# CPU_Dev_revA_1.net
KiCad netlist of a schematic drawn in EAGLE
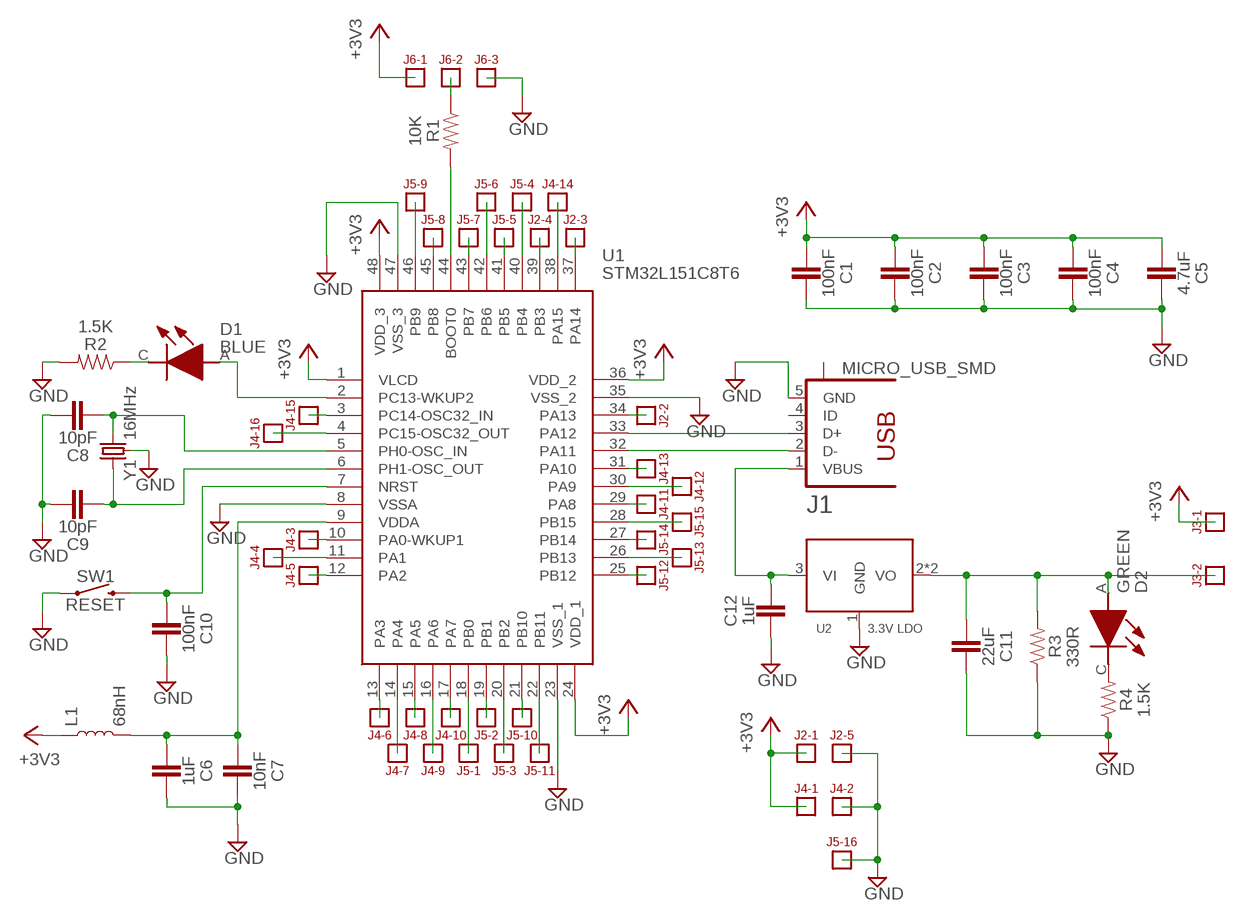
[diagram p0: schematic, sheet 1]

(export (version "E")
  (design (tool "Eeschema 10.0.6"))
  (components
    (comp (ref "C1")
      (value "100nF")
      (footprint "eagle-import:0402")
      (libsource (lib "eagle-import") (part "C_0402"))
    )
    (comp (ref "C2")
      (value "100nF")
      (footprint "eagle-import:0402")
      (libsource (lib "eagle-import") (part "C_0402"))
    )
    (comp (ref "C3")
      (value "100nF")
      (footprint "eagle-import:0402")
      (libsource (lib "eagle-import") (part "C_0402"))
    )
    (comp (ref "C4")
      (value "100nF")
      (footprint "eagle-import:0402")
      (libsource (lib "eagle-import") (part "C_0402"))
    )
    (comp (ref "C5")
      (value "4.7uF")
      (footprint "eagle-import:0402")
      (libsource (lib "eagle-import") (part "C_0402"))
    )
    (comp (ref "C6")
      (value "1uF")
      (footprint "eagle-import:0402")
      (libsource (lib "eagle-import") (part "C_0402"))
    )
    (comp (ref "C7")
      (value "10nF")
      (footprint "eagle-import:0402")
      (libsource (lib "eagle-import") (part "C_0402"))
    )
    (comp (ref "C8")
      (value "10pF")
      (footprint "eagle-import:0402")
      (libsource (lib "eagle-import") (part "C_0402"))
    )
    (comp (ref "C9")
      (value "10pF")
      (footprint "eagle-import:0402")
      (libsource (lib "eagle-import") (part "C_0402"))
    )
    (comp (ref "C10")
      (value "100nF")
      (footprint "eagle-import:0402")
      (libsource (lib "eagle-import") (part "C_0402"))
    )
    (comp (ref "C11")
      (value "22uF")
      (footprint "eagle-import:1206")
      (libsource (lib "eagle-import") (part "C_1206"))
    )
    (comp (ref "C12")
      (value "1uF")
      (footprint "eagle-import:0402")
      (libsource (lib "eagle-import") (part "C_0402"))
    )
    (comp (ref "D1")
      (value "BLUE")
      (footprint "eagle-import:LED_0603")
      (libsource (lib "eagle-import") (part "LED_0603"))
    )
    (comp (ref "D2")
      (value "GREEN")
      (footprint "eagle-import:LED_0603")
      (libsource (lib "eagle-import") (part "LED_0603"))
    )
    (comp (ref "J1")
      (value "MICRO_USB_SMD")
      (footprint "eagle-import:10118192-0002LF")
      (libsource (lib "eagle-import") (part "MICRO_USB_SMD"))
    )
    (comp (ref "J2")
      (value "HEADER_5PIN")
      (footprint "eagle-import:HEADER_5PIN")
      (libsource (lib "eagle-import") (part "HEADER_5PIN"))
    )
    (comp (ref "J3")
      (value "HEADER_2PIN")
      (footprint "eagle-import:HEADER_2PIN")
      (libsource (lib "eagle-import") (part "HEADER_2PIN"))
    )
    (comp (ref "J4")
      (value "HEADER_16PIN")
      (footprint "eagle-import:HEADER_16PIN")
      (libsource (lib "eagle-import") (part "HEADER_16PIN"))
    )
    (comp (ref "J5")
      (value "HEADER_16PIN")
      (footprint "eagle-import:HEADER_16PIN")
      (libsource (lib "eagle-import") (part "HEADER_16PIN"))
    )
    (comp (ref "J6")
      (value "HEADER_3PIN")
      (footprint "eagle-import:HEADER_3PIN")
      (libsource (lib "eagle-import") (part "HEADER_3PIN"))
    )
    (comp (ref "L1")
      (value "68nH")
      (footprint "eagle-import:0603")
      (libsource (lib "eagle-import") (part "L_0603"))
    )
    (comp (ref "R1")
      (value "10K")
      (footprint "eagle-import:0402")
      (libsource (lib "eagle-import") (part "R_0402"))
    )
    (comp (ref "R2")
      (value "1.5K")
      (footprint "eagle-import:0402")
      (libsource (lib "eagle-import") (part "R_0402"))
    )
    (comp (ref "R3")
      (value "330R")
      (footprint "eagle-import:0402")
      (libsource (lib "eagle-import") (part "R_0402"))
    )
    (comp (ref "R4")
      (value "1.5K")
      (footprint "eagle-import:0402")
      (libsource (lib "eagle-import") (part "R_0402"))
    )
    (comp (ref "SW1")
      (value "RESET")
      (footprint "eagle-import:PUSHBUTTON_SMD")
      (libsource (lib "eagle-import") (part "PUSHBUTTON_SMD"))
    )
    (comp (ref "U1")
      (value "STM32L151C8T6")
      (footprint "eagle-import:LQFP-48_7X7")
      (fields (field (name "MOUSER_PART_NUMBER") "511-STM32L151C8T6"))
      (libsource (lib "eagle-import") (part "STM32L151C8T6"))
    )
    (comp (ref "U2")
      (value "3.3V LDO")
      (footprint "eagle-import:SOT223")
      (libsource (lib "eagle-import") (part "VREG_SOT223"))
    )
    (comp (ref "Y1")
      (value "16MHz")
      (footprint "eagle-import:SMD3225-4P")
      (libsource (lib "eagle-import") (part "XTAL_SMD3225-4P"))
    )
  )
  (nets
    (net (code "1") (name "+3V3") (class "Default")
      (node (ref "C1") (pin "1") (pinfunction "1_1") (pintype "passive"))
      (node (ref "C2") (pin "1") (pinfunction "1_1") (pintype "passive"))
      (node (ref "C3") (pin "1") (pinfunction "1_1") (pintype "passive"))
      (node (ref "C4") (pin "1") (pinfunction "1_1") (pintype "passive"))
      (node (ref "C5") (pin "1") (pinfunction "1_1") (pintype "passive"))
      (node (ref "J2") (pin "P$1") (pinfunction "P$1_P$1") (pintype "bidirectional"))
      (node (ref "J3") (pin "P$1") (pinfunction "P$1_P$1") (pintype "bidirectional"))
      (node (ref "J4") (pin "P$1") (pinfunction "P$1_P$1") (pintype "bidirectional"))
      (node (ref "J6") (pin "P$1") (pinfunction "P$1_P$1") (pintype "bidirectional"))
      (node (ref "L1") (pin "1") (pinfunction "1_1") (pintype "passive"))
      (node (ref "U1") (pin "1") (pinfunction "VLCD_1") (pintype "bidirectional"))
      (node (ref "U1") (pin "24") (pinfunction "VDD_1_24") (pintype "bidirectional"))
      (node (ref "U1") (pin "36") (pinfunction "VDD_2_36") (pintype "bidirectional"))
      (node (ref "U1") (pin "48") (pinfunction "VDD_3_48") (pintype "bidirectional"))
    )
    (net (code "2") (name "GND") (class "Default")
      (node (ref "C1") (pin "2") (pinfunction "2_2") (pintype "passive"))
      (node (ref "C10") (pin "2") (pinfunction "2_2") (pintype "passive"))
      (node (ref "C11") (pin "2") (pinfunction "2_2") (pintype "passive"))
      (node (ref "C12") (pin "1") (pinfunction "1_1") (pintype "passive"))
      (node (ref "C2") (pin "2") (pinfunction "2_2") (pintype "passive"))
      (node (ref "C3") (pin "2") (pinfunction "2_2") (pintype "passive"))
      (node (ref "C4") (pin "2") (pinfunction "2_2") (pintype "passive"))
      (node (ref "C5") (pin "2") (pinfunction "2_2") (pintype "passive"))
      (node (ref "C6") (pin "2") (pinfunction "2_2") (pintype "passive"))
      (node (ref "C7") (pin "2") (pinfunction "2_2") (pintype "passive"))
      (node (ref "C8") (pin "2") (pinfunction "2_2") (pintype "passive"))
      (node (ref "C9") (pin "2") (pinfunction "2_2") (pintype "passive"))
      (node (ref "J1") (pin "5") (pinfunction "GND_5") (pintype "passive"))
      (node (ref "J2") (pin "P$5") (pinfunction "P$1_P$5") (pintype "bidirectional"))
      (node (ref "J4") (pin "P$2") (pinfunction "P$1_P$2") (pintype "bidirectional"))
      (node (ref "J5") (pin "P$16") (pinfunction "P$1_P$16") (pintype "bidirectional"))
      (node (ref "J6") (pin "P$3") (pinfunction "P$1_P$3") (pintype "bidirectional"))
      (node (ref "R2") (pin "2") (pinfunction "2_2") (pintype "passive"))
      (node (ref "R3") (pin "1") (pinfunction "1_1") (pintype "passive"))
      (node (ref "R4") (pin "1") (pinfunction "1_1") (pintype "passive"))
      (node (ref "SW1") (pin "A1") (pinfunction "1_A1") (pintype "passive"))
      (node (ref "SW1") (pin "B1") (pinfunction "1_B1") (pintype "passive"))
      (node (ref "U1") (pin "23") (pinfunction "VSS_1_23") (pintype "bidirectional"))
      (node (ref "U1") (pin "35") (pinfunction "VSS_2_35") (pintype "bidirectional"))
      (node (ref "U1") (pin "47") (pinfunction "VSS_3_47") (pintype "bidirectional"))
      (node (ref "U1") (pin "8") (pinfunction "VSSA_8") (pintype "bidirectional"))
      (node (ref "U2") (pin "1") (pinfunction "GND_1") (pintype "bidirectional"))
      (node (ref "Y1") (pin "2") (pinfunction "3_2") (pintype "passive"))
      (node (ref "Y1") (pin "4") (pinfunction "3_4") (pintype "passive"))
    )
    (net (code "3") (name "Net-(D1-K)") (class "Default")
      (node (ref "D1") (pin "C") (pinfunction "K_C") (pintype "bidirectional"))
      (node (ref "R2") (pin "1") (pinfunction "1_1") (pintype "passive"))
    )
    (net (code "4") (name "Net-(D2-K)") (class "Default")
      (node (ref "D2") (pin "C") (pinfunction "K_C") (pintype "bidirectional"))
      (node (ref "R4") (pin "2") (pinfunction "2_2") (pintype "passive"))
    )
    (net (code "5") (name "Net-(J1-D+)") (class "Default")
      (node (ref "J1") (pin "3") (pinfunction "D+_3") (pintype "passive"))
      (node (ref "U1") (pin "33") (pinfunction "PA12_33") (pintype "bidirectional"))
    )
    (net (code "6") (name "Net-(J1-D-)") (class "Default")
      (node (ref "J1") (pin "2") (pinfunction "D-_2") (pintype "passive"))
      (node (ref "U1") (pin "32") (pinfunction "PA11_32") (pintype "bidirectional"))
    )
    (net (code "7") (name "Net-(J1-VBUS)") (class "Default")
      (node (ref "C12") (pin "2") (pinfunction "2_2") (pintype "passive"))
      (node (ref "J1") (pin "1") (pinfunction "VBUS_1") (pintype "passive"))
      (node (ref "U2") (pin "3") (pinfunction "VI_3") (pintype "bidirectional"))
    )
    (net (code "8") (name "Net-(J2B-P$1)") (class "Default")
      (node (ref "J2") (pin "P$2") (pinfunction "P$1_P$2") (pintype "bidirectional"))
      (node (ref "U1") (pin "34") (pinfunction "PA13_34") (pintype "bidirectional"))
    )
    (net (code "9") (name "Net-(J2C-P$1)") (class "Default")
      (node (ref "J2") (pin "P$3") (pinfunction "P$1_P$3") (pintype "bidirectional"))
      (node (ref "U1") (pin "37") (pinfunction "PA14_37") (pintype "bidirectional"))
    )
    (net (code "10") (name "Net-(J2D-P$1)") (class "Default")
      (node (ref "J2") (pin "P$4") (pinfunction "P$1_P$4") (pintype "bidirectional"))
      (node (ref "U1") (pin "39") (pinfunction "PB3_39") (pintype "bidirectional"))
    )
    (net (code "11") (name "Net-(J3B-P$1)") (class "Default")
      (node (ref "C11") (pin "1") (pinfunction "1_1") (pintype "passive"))
      (node (ref "D2") (pin "A") (pinfunction "A_A") (pintype "bidirectional"))
      (node (ref "J3") (pin "P$2") (pinfunction "P$1_P$2") (pintype "bidirectional"))
      (node (ref "R3") (pin "2") (pinfunction "2_2") (pintype "passive"))
      (node (ref "U2") (pin "2") (pinfunction "VO_2") (pintype "bidirectional"))
      (node (ref "U2") (pin "4") (pinfunction "VO_4") (pintype "bidirectional"))
    )
    (net (code "12") (name "Net-(J4B-P$1)") (class "Default")
      (node (ref "J4") (pin "P$10") (pinfunction "P$1_P$10") (pintype "bidirectional"))
      (node (ref "U1") (pin "17") (pinfunction "PA7_17") (pintype "bidirectional"))
    )
    (net (code "13") (name "Net-(J4C-P$1)") (class "Default")
      (node (ref "J4") (pin "P$11") (pinfunction "P$1_P$11") (pintype "bidirectional"))
      (node (ref "U1") (pin "29") (pinfunction "PA8_29") (pintype "bidirectional"))
    )
    (net (code "14") (name "Net-(J4D-P$1)") (class "Default")
      (node (ref "J4") (pin "P$12") (pinfunction "P$1_P$12") (pintype "bidirectional"))
      (node (ref "U1") (pin "30") (pinfunction "PA9_30") (pintype "bidirectional"))
    )
    (net (code "15") (name "Net-(J4E-P$1)") (class "Default")
      (node (ref "J4") (pin "P$13") (pinfunction "P$1_P$13") (pintype "bidirectional"))
      (node (ref "U1") (pin "31") (pinfunction "PA10_31") (pintype "bidirectional"))
    )
    (net (code "16") (name "Net-(J4F-P$1)") (class "Default")
      (node (ref "J4") (pin "P$14") (pinfunction "P$1_P$14") (pintype "bidirectional"))
      (node (ref "U1") (pin "38") (pinfunction "PA15_38") (pintype "bidirectional"))
    )
    (net (code "17") (name "Net-(J4G-P$1)") (class "Default")
      (node (ref "J4") (pin "P$15") (pinfunction "P$1_P$15") (pintype "bidirectional"))
      (node (ref "U1") (pin "3") (pinfunction "PC14-OSC32_IN_3") (pintype "bidirectional"))
    )
    (net (code "18") (name "Net-(J4H-P$1)") (class "Default")
      (node (ref "J4") (pin "P$16") (pinfunction "P$1_P$16") (pintype "bidirectional"))
      (node (ref "U1") (pin "4") (pinfunction "PC15-OSC32_OUT_4") (pintype "bidirectional"))
    )
    (net (code "19") (name "Net-(J4J-P$1)") (class "Default")
      (node (ref "J4") (pin "P$3") (pinfunction "P$1_P$3") (pintype "bidirectional"))
      (node (ref "U1") (pin "10") (pinfunction "PA0-WKUP1_10") (pintype "bidirectional"))
    )
    (net (code "20") (name "Net-(J4K-P$1)") (class "Default")
      (node (ref "J4") (pin "P$4") (pinfunction "P$1_P$4") (pintype "bidirectional"))
      (node (ref "U1") (pin "11") (pinfunction "PA1_11") (pintype "bidirectional"))
    )
    (net (code "21") (name "Net-(J4L-P$1)") (class "Default")
      (node (ref "J4") (pin "P$5") (pinfunction "P$1_P$5") (pintype "bidirectional"))
      (node (ref "U1") (pin "12") (pinfunction "PA2_12") (pintype "bidirectional"))
    )
    (net (code "22") (name "Net-(J4M-P$1)") (class "Default")
      (node (ref "J4") (pin "P$6") (pinfunction "P$1_P$6") (pintype "bidirectional"))
      (node (ref "U1") (pin "13") (pinfunction "PA3_13") (pintype "bidirectional"))
    )
    (net (code "23") (name "Net-(J4N-P$1)") (class "Default")
      (node (ref "J4") (pin "P$7") (pinfunction "P$1_P$7") (pintype "bidirectional"))
      (node (ref "U1") (pin "14") (pinfunction "PA4_14") (pintype "bidirectional"))
    )
    (net (code "24") (name "Net-(J4O-P$1)") (class "Default")
      (node (ref "J4") (pin "P$8") (pinfunction "P$1_P$8") (pintype "bidirectional"))
      (node (ref "U1") (pin "15") (pinfunction "PA5_15") (pintype "bidirectional"))
    )
    (net (code "25") (name "Net-(J4P-P$1)") (class "Default")
      (node (ref "J4") (pin "P$9") (pinfunction "P$1_P$9") (pintype "bidirectional"))
      (node (ref "U1") (pin "16") (pinfunction "PA6_16") (pintype "bidirectional"))
    )
    (net (code "26") (name "Net-(J5B-P$1)") (class "Default")
      (node (ref "J5") (pin "P$10") (pinfunction "P$1_P$10") (pintype "bidirectional"))
      (node (ref "U1") (pin "21") (pinfunction "PB10_21") (pintype "bidirectional"))
    )
    (net (code "27") (name "Net-(J5C-P$1)") (class "Default")
      (node (ref "J5") (pin "P$11") (pinfunction "P$1_P$11") (pintype "bidirectional"))
      (node (ref "U1") (pin "22") (pinfunction "PB11_22") (pintype "bidirectional"))
    )
    (net (code "28") (name "Net-(J5D-P$1)") (class "Default")
      (node (ref "J5") (pin "P$12") (pinfunction "P$1_P$12") (pintype "bidirectional"))
      (node (ref "U1") (pin "25") (pinfunction "PB12_25") (pintype "bidirectional"))
    )
    (net (code "29") (name "Net-(J5E-P$1)") (class "Default")
      (node (ref "J5") (pin "P$13") (pinfunction "P$1_P$13") (pintype "bidirectional"))
      (node (ref "U1") (pin "26") (pinfunction "PB13_26") (pintype "bidirectional"))
    )
    (net (code "30") (name "Net-(J5F-P$1)") (class "Default")
      (node (ref "J5") (pin "P$14") (pinfunction "P$1_P$14") (pintype "bidirectional"))
      (node (ref "U1") (pin "27") (pinfunction "PB14_27") (pintype "bidirectional"))
    )
    (net (code "31") (name "Net-(J5G-P$1)") (class "Default")
      (node (ref "J5") (pin "P$15") (pinfunction "P$1_P$15") (pintype "bidirectional"))
      (node (ref "U1") (pin "28") (pinfunction "PB15_28") (pintype "bidirectional"))
    )
    (net (code "32") (name "Net-(J5I-P$1)") (class "Default")
      (node (ref "J5") (pin "P$2") (pinfunction "P$1_P$2") (pintype "bidirectional"))
      (node (ref "U1") (pin "19") (pinfunction "PB1_19") (pintype "bidirectional"))
    )
    (net (code "33") (name "Net-(J5J-P$1)") (class "Default")
      (node (ref "J5") (pin "P$3") (pinfunction "P$1_P$3") (pintype "bidirectional"))
      (node (ref "U1") (pin "20") (pinfunction "PB2_20") (pintype "bidirectional"))
    )
    (net (code "34") (name "Net-(J5K-P$1)") (class "Default")
      (node (ref "J5") (pin "P$4") (pinfunction "P$1_P$4") (pintype "bidirectional"))
      (node (ref "U1") (pin "40") (pinfunction "PB4_40") (pintype "bidirectional"))
    )
    (net (code "35") (name "Net-(J5L-P$1)") (class "Default")
      (node (ref "J5") (pin "P$5") (pinfunction "P$1_P$5") (pintype "bidirectional"))
      (node (ref "U1") (pin "41") (pinfunction "PB5_41") (pintype "bidirectional"))
    )
    (net (code "36") (name "Net-(J5M-P$1)") (class "Default")
      (node (ref "J5") (pin "P$6") (pinfunction "P$1_P$6") (pintype "bidirectional"))
      (node (ref "U1") (pin "42") (pinfunction "PB6_42") (pintype "bidirectional"))
    )
    (net (code "37") (name "Net-(J5N-P$1)") (class "Default")
      (node (ref "J5") (pin "P$7") (pinfunction "P$1_P$7") (pintype "bidirectional"))
      (node (ref "U1") (pin "43") (pinfunction "PB7_43") (pintype "bidirectional"))
    )
    (net (code "38") (name "Net-(J5O-P$1)") (class "Default")
      (node (ref "J5") (pin "P$8") (pinfunction "P$1_P$8") (pintype "bidirectional"))
      (node (ref "U1") (pin "45") (pinfunction "PB8_45") (pintype "bidirectional"))
    )
    (net (code "39") (name "Net-(J5P-P$1)") (class "Default")
      (node (ref "J5") (pin "P$9") (pinfunction "P$1_P$9") (pintype "bidirectional"))
      (node (ref "U1") (pin "46") (pinfunction "PB9_46") (pintype "bidirectional"))
    )
    (net (code "40") (name "Net-(J6B-P$1)") (class "Default")
      (node (ref "J6") (pin "P$2") (pinfunction "P$1_P$2") (pintype "bidirectional"))
      (node (ref "R1") (pin "1") (pinfunction "1_1") (pintype "passive"))
    )
    (net (code "41") (name "Net-(U1-BOOT0)") (class "Default")
      (node (ref "R1") (pin "2") (pinfunction "2_2") (pintype "passive"))
      (node (ref "U1") (pin "44") (pinfunction "BOOT0_44") (pintype "bidirectional"))
    )
    (net (code "42") (name "Net-(U1-NRST)") (class "Default")
      (node (ref "C10") (pin "1") (pinfunction "1_1") (pintype "passive"))
      (node (ref "SW1") (pin "C1") (pinfunction "2_C1") (pintype "passive"))
      (node (ref "SW1") (pin "D1") (pinfunction "2_D1") (pintype "passive"))
      (node (ref "U1") (pin "7") (pinfunction "NRST_7") (pintype "bidirectional"))
    )
    (net (code "43") (name "Net-(U1-PB0)") (class "Default")
      (node (ref "J5") (pin "P$1") (pinfunction "P$1_P$1") (pintype "bidirectional"))
      (node (ref "U1") (pin "18") (pinfunction "PB0_18") (pintype "bidirectional"))
    )
    (net (code "44") (name "Net-(U1-PC13-WKUP2)") (class "Default")
      (node (ref "D1") (pin "A") (pinfunction "A_A") (pintype "bidirectional"))
      (node (ref "U1") (pin "2") (pinfunction "PC13-WKUP2_2") (pintype "bidirectional"))
    )
    (net (code "45") (name "Net-(U1-PH0-OSC_IN)") (class "Default")
      (node (ref "C8") (pin "1") (pinfunction "1_1") (pintype "passive"))
      (node (ref "U1") (pin "5") (pinfunction "PH0-OSC_IN_5") (pintype "bidirectional"))
      (node (ref "Y1") (pin "3") (pinfunction "2_3") (pintype "passive"))
    )
    (net (code "46") (name "Net-(U1-PH1-OSC_OUT)") (class "Default")
      (node (ref "C9") (pin "1") (pinfunction "1_1") (pintype "passive"))
      (node (ref "U1") (pin "6") (pinfunction "PH1-OSC_OUT_6") (pintype "bidirectional"))
      (node (ref "Y1") (pin "1") (pinfunction "1_1") (pintype "passive"))
    )
    (net (code "47") (name "Net-(U1-VDDA)") (class "Default")
      (node (ref "C6") (pin "1") (pinfunction "1_1") (pintype "passive"))
      (node (ref "C7") (pin "1") (pinfunction "1_1") (pintype "passive"))
      (node (ref "L1") (pin "2") (pinfunction "2_2") (pintype "passive"))
      (node (ref "U1") (pin "9") (pinfunction "VDDA_9") (pintype "bidirectional"))
    )
    (net (code "48") (name "unconnected-(J1-ID-Pad4)") (class "Default")
      (node (ref "J1") (pin "4") (pinfunction "ID_4") (pintype "passive"))
    )
    (net (code "49") (name "unconnected-(J1-PadS1)") (class "Default")
      (node (ref "J1") (pin "S1") (pinfunction "S1_S1") (pintype "passive"))
    )
  )
)
